# ArduinoBoardMK1.net
KiCad netlist of a schematic drawn in EAGLE
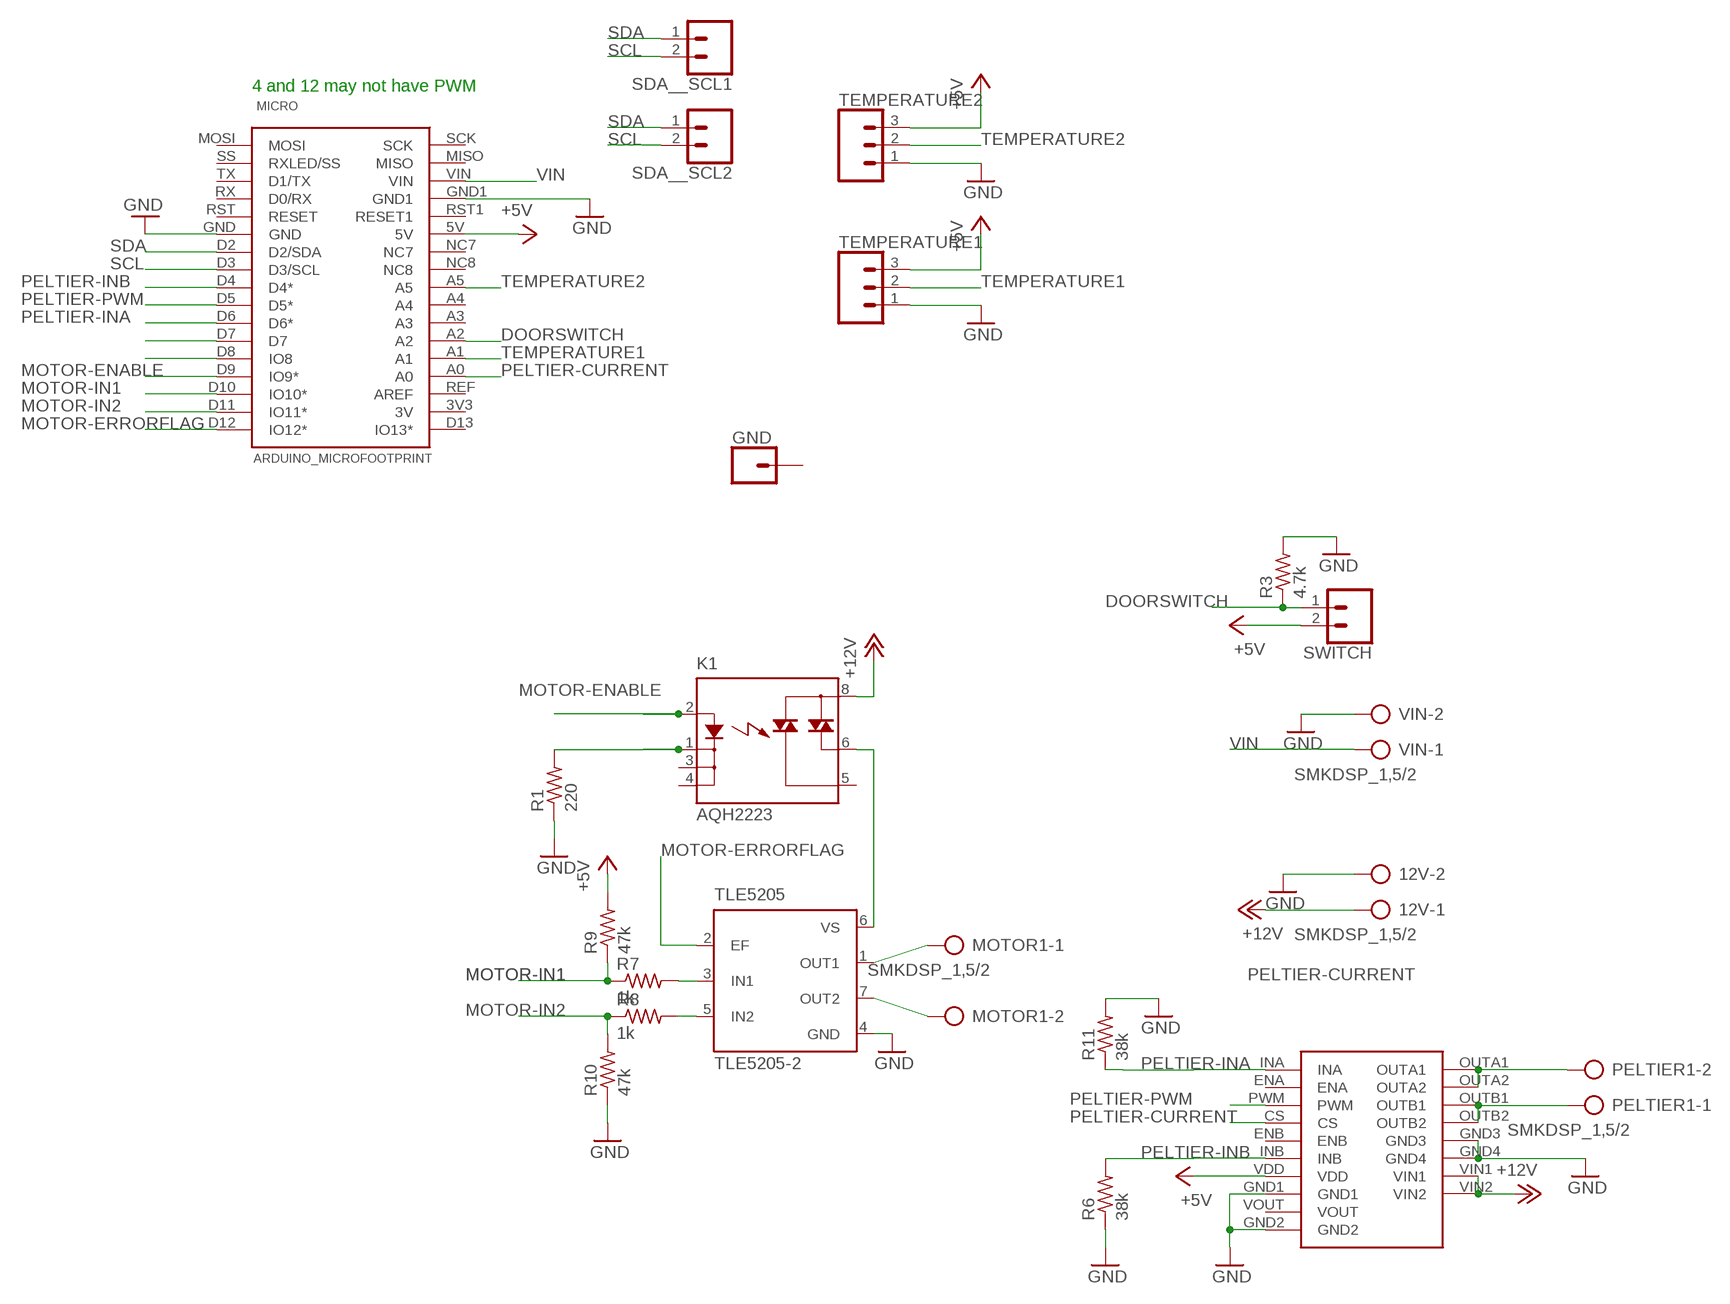
[diagram p0: schematic, sheet 1]

(export (version "E")
  (design (tool "Eeschema 10.0.6"))
  (components
    (comp (ref "12V")
      (value "SMKDSP_1,5/2")
      (footprint "eagle-import:SMKDSP_1,5_2")
      (fields (field (name "MF") "FARNELL") (field (name "MPN") "1733570"))
      (libsource (lib "eagle-import") (part "SMKDSP_1,5/2"))
    )
    (comp (ref "GND")
      (value "CONN_01")
      (footprint "eagle-import:1X01")
      (libsource (lib "eagle-import") (part "CONN_01"))
    )
    (comp (ref "K1")
      (value "AQH2223")
      (footprint "eagle-import:DIL07")
      (fields (field (name "MF") "AROMAT/ MATSUSHITA"))
      (libsource (lib "eagle-import") (part "AQH2232"))
    )
    (comp (ref "MICRO")
      (value "ARDUINO_MICROFOOTPRINT")
      (footprint "eagle-import:ARDUINO-MICRO")
      (libsource (lib "eagle-import") (part "ARDUINO_MICROFOOTPRINT"))
    )
    (comp (ref "MOTOR1")
      (value "SMKDSP_1,5/2")
      (footprint "eagle-import:SMKDSP_1,5_2")
      (fields (field (name "MF") "FARNELL") (field (name "MPN") "1733570"))
      (libsource (lib "eagle-import") (part "SMKDSP_1,5/2"))
    )
    (comp (ref "PELTIER1")
      (value "SMKDSP_1,5/2")
      (footprint "eagle-import:SMKDSP_1,5_2")
      (fields (field (name "MF") "FARNELL") (field (name "MPN") "1733570"))
      (libsource (lib "eagle-import") (part "SMKDSP_1,5/2"))
    )
    (comp (ref "R1")
      (value "220")
      (footprint "eagle-import:0207_12")
      (libsource (lib "eagle-import") (part "R-US_0207/12"))
    )
    (comp (ref "R3")
      (value "4.7k")
      (footprint "eagle-import:0207_12")
      (libsource (lib "eagle-import") (part "R-US_0207/12"))
    )
    (comp (ref "R6")
      (value "38k")
      (footprint "eagle-import:0207_12")
      (libsource (lib "eagle-import") (part "R-US_0207/12"))
    )
    (comp (ref "R7")
      (value "1k")
      (footprint "eagle-import:0207_12")
      (libsource (lib "eagle-import") (part "R-US_0207/12"))
    )
    (comp (ref "R8")
      (value "1k")
      (footprint "eagle-import:0207_12")
      (libsource (lib "eagle-import") (part "R-US_0207/12"))
    )
    (comp (ref "R9")
      (value "47k")
      (footprint "eagle-import:0207_12")
      (libsource (lib "eagle-import") (part "R-US_0207/12"))
    )
    (comp (ref "R10")
      (value "47k")
      (footprint "eagle-import:0207_12")
      (libsource (lib "eagle-import") (part "R-US_0207/12"))
    )
    (comp (ref "R11")
      (value "38k")
      (footprint "eagle-import:0207_12")
      (libsource (lib "eagle-import") (part "R-US_0207/12"))
    )
    (comp (ref "SDA__SCL1")
      (value "CONN_02PTH3")
      (footprint "eagle-import:1X02_LONGPADS")
      (libsource (lib "eagle-import") (part "CONN_02PTH3"))
    )
    (comp (ref "SDA__SCL2")
      (value "CONN_02PTH3")
      (footprint "eagle-import:1X02_LONGPADS")
      (libsource (lib "eagle-import") (part "CONN_02PTH3"))
    )
    (comp (ref "SWITCH")
      (value "CONN_02PTH3")
      (footprint "eagle-import:1X02_LONGPADS")
      (libsource (lib "eagle-import") (part "CONN_02PTH3"))
    )
    (comp (ref "TEMPERATURE1")
      (value "CONN_03LONGPADS")
      (footprint "eagle-import:1X03_LONGPADS")
      (libsource (lib "eagle-import") (part "CONN_03LONGPADS"))
    )
    (comp (ref "TEMPERATURE2")
      (value "CONN_03LONGPADS")
      (footprint "eagle-import:1X03_LONGPADS")
      (libsource (lib "eagle-import") (part "CONN_03LONGPADS"))
    )
    (comp (ref "TLE5205")
      (value "TLE5205-2")
      (footprint "eagle-import:P-TO220-7-11")
      (libsource (lib "eagle-import") (part "TLE5205-2"))
    )
    (comp (ref "VIN")
      (value "SMKDSP_1,5/2")
      (footprint "eagle-import:SMKDSP_1,5_2")
      (fields (field (name "MF") "FARNELL") (field (name "MPN") "1733570"))
      (libsource (lib "eagle-import") (part "SMKDSP_1,5/2"))
    )
    (comp (ref "VNH5019")
      (value "VNH5019VNH5019BOARD")
      (footprint "eagle-import:DIP3302W60P254L2400H500Q20B")
      (libsource (lib "eagle-import") (part "VNH5019VNH5019BOARD"))
    )
  )
  (nets
    (net (code "1") (name "+5V") (class "Default")
      (node (ref "MICRO") (pin "5V") (pinfunction "5V_5V") (pintype "bidirectional"))
      (node (ref "R9") (pin "2") (pinfunction "2_2") (pintype "passive"))
      (node (ref "SWITCH") (pin "2") (pinfunction "2_2") (pintype "passive"))
      (node (ref "TEMPERATURE1") (pin "3") (pinfunction "3_3") (pintype "passive"))
      (node (ref "TEMPERATURE2") (pin "3") (pinfunction "3_3") (pintype "passive"))
      (node (ref "VNH5019") (pin "VDD") (pinfunction "VDD_VDD") (pintype "bidirectional"))
    )
    (net (code "2") (name "+12V") (class "Default")
      (node (ref "12V") (pin "1") (pinfunction "KL_1") (pintype "passive"))
      (node (ref "K1") (pin "8") (pinfunction "DS1_8") (pintype "passive"))
      (node (ref "VNH5019") (pin "VIN1") (pinfunction "VIN1_VIN1") (pintype "bidirectional"))
      (node (ref "VNH5019") (pin "VIN2") (pinfunction "VIN2_VIN2") (pintype "bidirectional"))
    )
    (net (code "3") (name "/DOORSWITCH") (class "Default")
      (node (ref "MICRO") (pin "A2") (pinfunction "A2_A2") (pintype "bidirectional"))
      (node (ref "R3") (pin "1") (pinfunction "1_1") (pintype "passive"))
      (node (ref "SWITCH") (pin "1") (pinfunction "1_1") (pintype "passive"))
    )
    (net (code "4") (name "/MOTOR-ENABLE") (class "Default")
      (node (ref "K1") (pin "2") (pinfunction "A_2") (pintype "passive"))
      (node (ref "MICRO") (pin "D9") (pinfunction "IO9*_D9") (pintype "bidirectional"))
    )
    (net (code "5") (name "/MOTOR-ERRORFLAG") (class "Default")
      (node (ref "MICRO") (pin "D12") (pinfunction "IO12*_D12") (pintype "bidirectional"))
      (node (ref "TLE5205") (pin "2") (pinfunction "EF_2") (pintype "open_collector"))
    )
    (net (code "6") (name "/MOTOR-IN1") (class "Default")
      (node (ref "MICRO") (pin "D10") (pinfunction "IO10*_D10") (pintype "bidirectional"))
      (node (ref "R7") (pin "1") (pinfunction "1_1") (pintype "passive"))
      (node (ref "R9") (pin "1") (pinfunction "1_1") (pintype "passive"))
    )
    (net (code "7") (name "/MOTOR-IN2") (class "Default")
      (node (ref "MICRO") (pin "D11") (pinfunction "IO11*_D11") (pintype "bidirectional"))
      (node (ref "R10") (pin "2") (pinfunction "2_2") (pintype "passive"))
      (node (ref "R8") (pin "1") (pinfunction "1_1") (pintype "passive"))
    )
    (net (code "8") (name "/PELTIER-CURRENT") (class "Default")
      (node (ref "MICRO") (pin "A0") (pinfunction "A0_A0") (pintype "bidirectional"))
      (node (ref "VNH5019") (pin "CS") (pinfunction "CS_CS") (pintype "bidirectional"))
    )
    (net (code "9") (name "/PELTIER-INA") (class "Default")
      (node (ref "MICRO") (pin "D6") (pinfunction "D6*_D6") (pintype "bidirectional"))
      (node (ref "R11") (pin "1") (pinfunction "1_1") (pintype "passive"))
      (node (ref "VNH5019") (pin "INA") (pinfunction "INA_INA") (pintype "bidirectional"))
    )
    (net (code "10") (name "/PELTIER-INB") (class "Default")
      (node (ref "MICRO") (pin "D4") (pinfunction "D4*_D4") (pintype "bidirectional"))
      (node (ref "R6") (pin "2") (pinfunction "2_2") (pintype "passive"))
      (node (ref "VNH5019") (pin "INB") (pinfunction "INB_INB") (pintype "bidirectional"))
    )
    (net (code "11") (name "/PELTIER-PWM") (class "Default")
      (node (ref "MICRO") (pin "D5") (pinfunction "D5*_D5") (pintype "bidirectional"))
      (node (ref "VNH5019") (pin "PWM") (pinfunction "PWM_PWM") (pintype "bidirectional"))
    )
    (net (code "12") (name "/SCL") (class "Default")
      (node (ref "MICRO") (pin "D3") (pinfunction "D3/SCL_D3") (pintype "bidirectional"))
      (node (ref "SDA__SCL1") (pin "2") (pinfunction "2_2") (pintype "passive"))
      (node (ref "SDA__SCL2") (pin "2") (pinfunction "2_2") (pintype "passive"))
    )
    (net (code "13") (name "/SDA") (class "Default")
      (node (ref "MICRO") (pin "D2") (pinfunction "D2/SDA_D2") (pintype "bidirectional"))
      (node (ref "SDA__SCL1") (pin "1") (pinfunction "1_1") (pintype "passive"))
      (node (ref "SDA__SCL2") (pin "1") (pinfunction "1_1") (pintype "passive"))
    )
    (net (code "14") (name "/TEMPERATURE1") (class "Default")
      (node (ref "MICRO") (pin "A1") (pinfunction "A1_A1") (pintype "bidirectional"))
      (node (ref "TEMPERATURE1") (pin "2") (pinfunction "2_2") (pintype "passive"))
    )
    (net (code "15") (name "/TEMPERATURE2") (class "Default")
      (node (ref "MICRO") (pin "A5") (pinfunction "A5_A5") (pintype "bidirectional"))
      (node (ref "TEMPERATURE2") (pin "2") (pinfunction "2_2") (pintype "passive"))
    )
    (net (code "16") (name "/VIN") (class "Default")
      (node (ref "MICRO") (pin "VIN") (pinfunction "VIN_VIN") (pintype "bidirectional"))
      (node (ref "VIN") (pin "1") (pinfunction "KL_1") (pintype "passive"))
    )
    (net (code "17") (name "GND") (class "Default")
      (node (ref "12V") (pin "2") (pinfunction "KL_2") (pintype "passive"))
      (node (ref "MICRO") (pin "GND") (pinfunction "GND_GND") (pintype "bidirectional"))
      (node (ref "MICRO") (pin "GND1") (pinfunction "GND1_GND1") (pintype "bidirectional"))
      (node (ref "R1") (pin "1") (pinfunction "1_1") (pintype "passive"))
      (node (ref "R10") (pin "1") (pinfunction "1_1") (pintype "passive"))
      (node (ref "R11") (pin "2") (pinfunction "2_2") (pintype "passive"))
      (node (ref "R3") (pin "2") (pinfunction "2_2") (pintype "passive"))
      (node (ref "R6") (pin "1") (pinfunction "1_1") (pintype "passive"))
      (node (ref "TEMPERATURE1") (pin "1") (pinfunction "1_1") (pintype "passive"))
      (node (ref "TEMPERATURE2") (pin "1") (pinfunction "1_1") (pintype "passive"))
      (node (ref "TLE5205") (pin "4") (pinfunction "GND_4") (pintype "power_in"))
      (node (ref "VIN") (pin "2") (pinfunction "KL_2") (pintype "passive"))
      (node (ref "VNH5019") (pin "GND1") (pinfunction "GND1_GND1") (pintype "bidirectional"))
      (node (ref "VNH5019") (pin "GND2") (pinfunction "GND2_GND2") (pintype "bidirectional"))
      (node (ref "VNH5019") (pin "GND3") (pinfunction "GND3_GND3") (pintype "bidirectional"))
      (node (ref "VNH5019") (pin "GND4") (pinfunction "GND4_GND4") (pintype "bidirectional"))
    )
    (net (code "18") (name "Net-(K1-DS3)") (class "Default")
      (node (ref "K1") (pin "6") (pinfunction "DS3_6") (pintype "passive"))
      (node (ref "TLE5205") (pin "6") (pinfunction "VS_6") (pintype "input"))
    )
    (net (code "19") (name "Net-(K1-K)") (class "Default")
      (node (ref "K1") (pin "1") (pinfunction "K_1") (pintype "passive"))
      (node (ref "R1") (pin "2") (pinfunction "2_2") (pintype "passive"))
    )
    (net (code "20") (name "Net-(MOTOR1A-KL)") (class "Default")
      (node (ref "MOTOR1") (pin "1") (pinfunction "KL_1") (pintype "passive"))
      (node (ref "TLE5205") (pin "1") (pinfunction "OUT1_1") (pintype "output"))
    )
    (net (code "21") (name "Net-(MOTOR1B-KL)") (class "Default")
      (node (ref "MOTOR1") (pin "2") (pinfunction "KL_2") (pintype "passive"))
      (node (ref "TLE5205") (pin "7") (pinfunction "OUT2_7") (pintype "output"))
    )
    (net (code "22") (name "Net-(PELTIER1A-KL)") (class "Default")
      (node (ref "PELTIER1") (pin "1") (pinfunction "KL_1") (pintype "passive"))
      (node (ref "VNH5019") (pin "OUTB1") (pinfunction "OUTB1_OUTB1") (pintype "bidirectional"))
      (node (ref "VNH5019") (pin "OUTB2") (pinfunction "OUTB2_OUTB2") (pintype "bidirectional"))
    )
    (net (code "23") (name "Net-(PELTIER1B-KL)") (class "Default")
      (node (ref "PELTIER1") (pin "2") (pinfunction "KL_2") (pintype "passive"))
      (node (ref "VNH5019") (pin "OUTA1") (pinfunction "OUTA1_OUTA1") (pintype "bidirectional"))
      (node (ref "VNH5019") (pin "OUTA2") (pinfunction "OUTA2_OUTA2") (pintype "bidirectional"))
    )
    (net (code "24") (name "Net-(TLE5205-IN1)") (class "Default")
      (node (ref "R7") (pin "2") (pinfunction "2_2") (pintype "passive"))
      (node (ref "TLE5205") (pin "3") (pinfunction "IN1_3") (pintype "input"))
    )
    (net (code "25") (name "Net-(TLE5205-IN2)") (class "Default")
      (node (ref "R8") (pin "2") (pinfunction "2_2") (pintype "passive"))
      (node (ref "TLE5205") (pin "5") (pinfunction "IN2_5") (pintype "input"))
    )
    (net (code "26") (name "unconnected-(GND-Pad1)") (class "Default")
      (node (ref "GND") (pin "1") (pinfunction "1_1") (pintype "passive"))
    )
    (net (code "27") (name "unconnected-(K1-DS2-Pad5)") (class "Default")
      (node (ref "K1") (pin "5") (pinfunction "DS2_5") (pintype "passive"))
    )
    (net (code "28") (name "unconnected-(K1-K1-Pad3)") (class "Default")
      (node (ref "K1") (pin "3") (pinfunction "K1_3") (pintype "passive"))
    )
    (net (code "29") (name "unconnected-(K1-K2-Pad4)") (class "Default")
      (node (ref "K1") (pin "4") (pinfunction "K2_4") (pintype "passive"))
    )
    (net (code "30") (name "unconnected-(MICRO-3V-Pad3V3)") (class "Default")
      (node (ref "MICRO") (pin "3V3") (pinfunction "3V_3V3") (pintype "bidirectional"))
    )
    (net (code "31") (name "unconnected-(MICRO-AREF-PadREF)") (class "Default")
      (node (ref "MICRO") (pin "REF") (pinfunction "AREF_REF") (pintype "bidirectional"))
    )
    (net (code "32") (name "unconnected-(MICRO-D0{slash}RX-PadRX)") (class "Default")
      (node (ref "MICRO") (pin "RX") (pinfunction "D0/RX_RX") (pintype "bidirectional"))
    )
    (net (code "33") (name "unconnected-(MICRO-D1{slash}TX-PadTX)") (class "Default")
      (node (ref "MICRO") (pin "TX") (pinfunction "D1/TX_TX") (pintype "bidirectional"))
    )
    (net (code "34") (name "unconnected-(MICRO-IO8-PadD8)") (class "Default")
      (node (ref "MICRO") (pin "D8") (pinfunction "IO8_D8") (pintype "bidirectional"))
    )
    (net (code "35") (name "unconnected-(MICRO-IO13*-PadD13)") (class "Default")
      (node (ref "MICRO") (pin "D13") (pinfunction "IO13*_D13") (pintype "bidirectional"))
    )
    (net (code "36") (name "unconnected-(MICRO-PadA3)") (class "Default")
      (node (ref "MICRO") (pin "A3") (pinfunction "A3_A3") (pintype "bidirectional"))
    )
    (net (code "37") (name "unconnected-(MICRO-PadA4)") (class "Default")
      (node (ref "MICRO") (pin "A4") (pinfunction "A4_A4") (pintype "bidirectional"))
    )
    (net (code "38") (name "unconnected-(MICRO-PadD7)") (class "Default")
      (node (ref "MICRO") (pin "D7") (pinfunction "D7_D7") (pintype "bidirectional"))
    )
    (net (code "39") (name "unconnected-(MICRO-PadMISO)") (class "Default")
      (node (ref "MICRO") (pin "MISO") (pinfunction "MISO_MISO") (pintype "bidirectional"))
    )
    (net (code "40") (name "unconnected-(MICRO-PadMOSI)") (class "Default")
      (node (ref "MICRO") (pin "MOSI") (pinfunction "MOSI_MOSI") (pintype "bidirectional"))
    )
    (net (code "41") (name "unconnected-(MICRO-PadNC7)") (class "Default")
      (node (ref "MICRO") (pin "NC7") (pinfunction "NC7_NC7") (pintype "bidirectional"))
    )
    (net (code "42") (name "unconnected-(MICRO-PadNC8)") (class "Default")
      (node (ref "MICRO") (pin "NC8") (pinfunction "NC8_NC8") (pintype "bidirectional"))
    )
    (net (code "43") (name "unconnected-(MICRO-PadSCK)") (class "Default")
      (node (ref "MICRO") (pin "SCK") (pinfunction "SCK_SCK") (pintype "bidirectional"))
    )
    (net (code "44") (name "unconnected-(MICRO-RESET-PadRST)") (class "Default")
      (node (ref "MICRO") (pin "RST") (pinfunction "RESET_RST") (pintype "bidirectional"))
    )
    (net (code "45") (name "unconnected-(MICRO-RESET1-PadRST1)") (class "Default")
      (node (ref "MICRO") (pin "RST1") (pinfunction "RESET1_RST1") (pintype "bidirectional"))
    )
    (net (code "46") (name "unconnected-(MICRO-RXLED{slash}SS-PadSS)") (class "Default")
      (node (ref "MICRO") (pin "SS") (pinfunction "RXLED/SS_SS") (pintype "bidirectional"))
    )
    (net (code "47") (name "unconnected-(VNH5019-PadENA)") (class "Default")
      (node (ref "VNH5019") (pin "ENA") (pinfunction "ENA_ENA") (pintype "bidirectional"))
    )
    (net (code "48") (name "unconnected-(VNH5019-PadENB)") (class "Default")
      (node (ref "VNH5019") (pin "ENB") (pinfunction "ENB_ENB") (pintype "bidirectional"))
    )
    (net (code "49") (name "unconnected-(VNH5019-PadVOUT)") (class "Default")
      (node (ref "VNH5019") (pin "VOUT") (pinfunction "VOUT_VOUT") (pintype "bidirectional"))
    )
  )
)
